# plc-6u-rs485-router.net
KiCad netlist of a schematic drawn in EAGLE
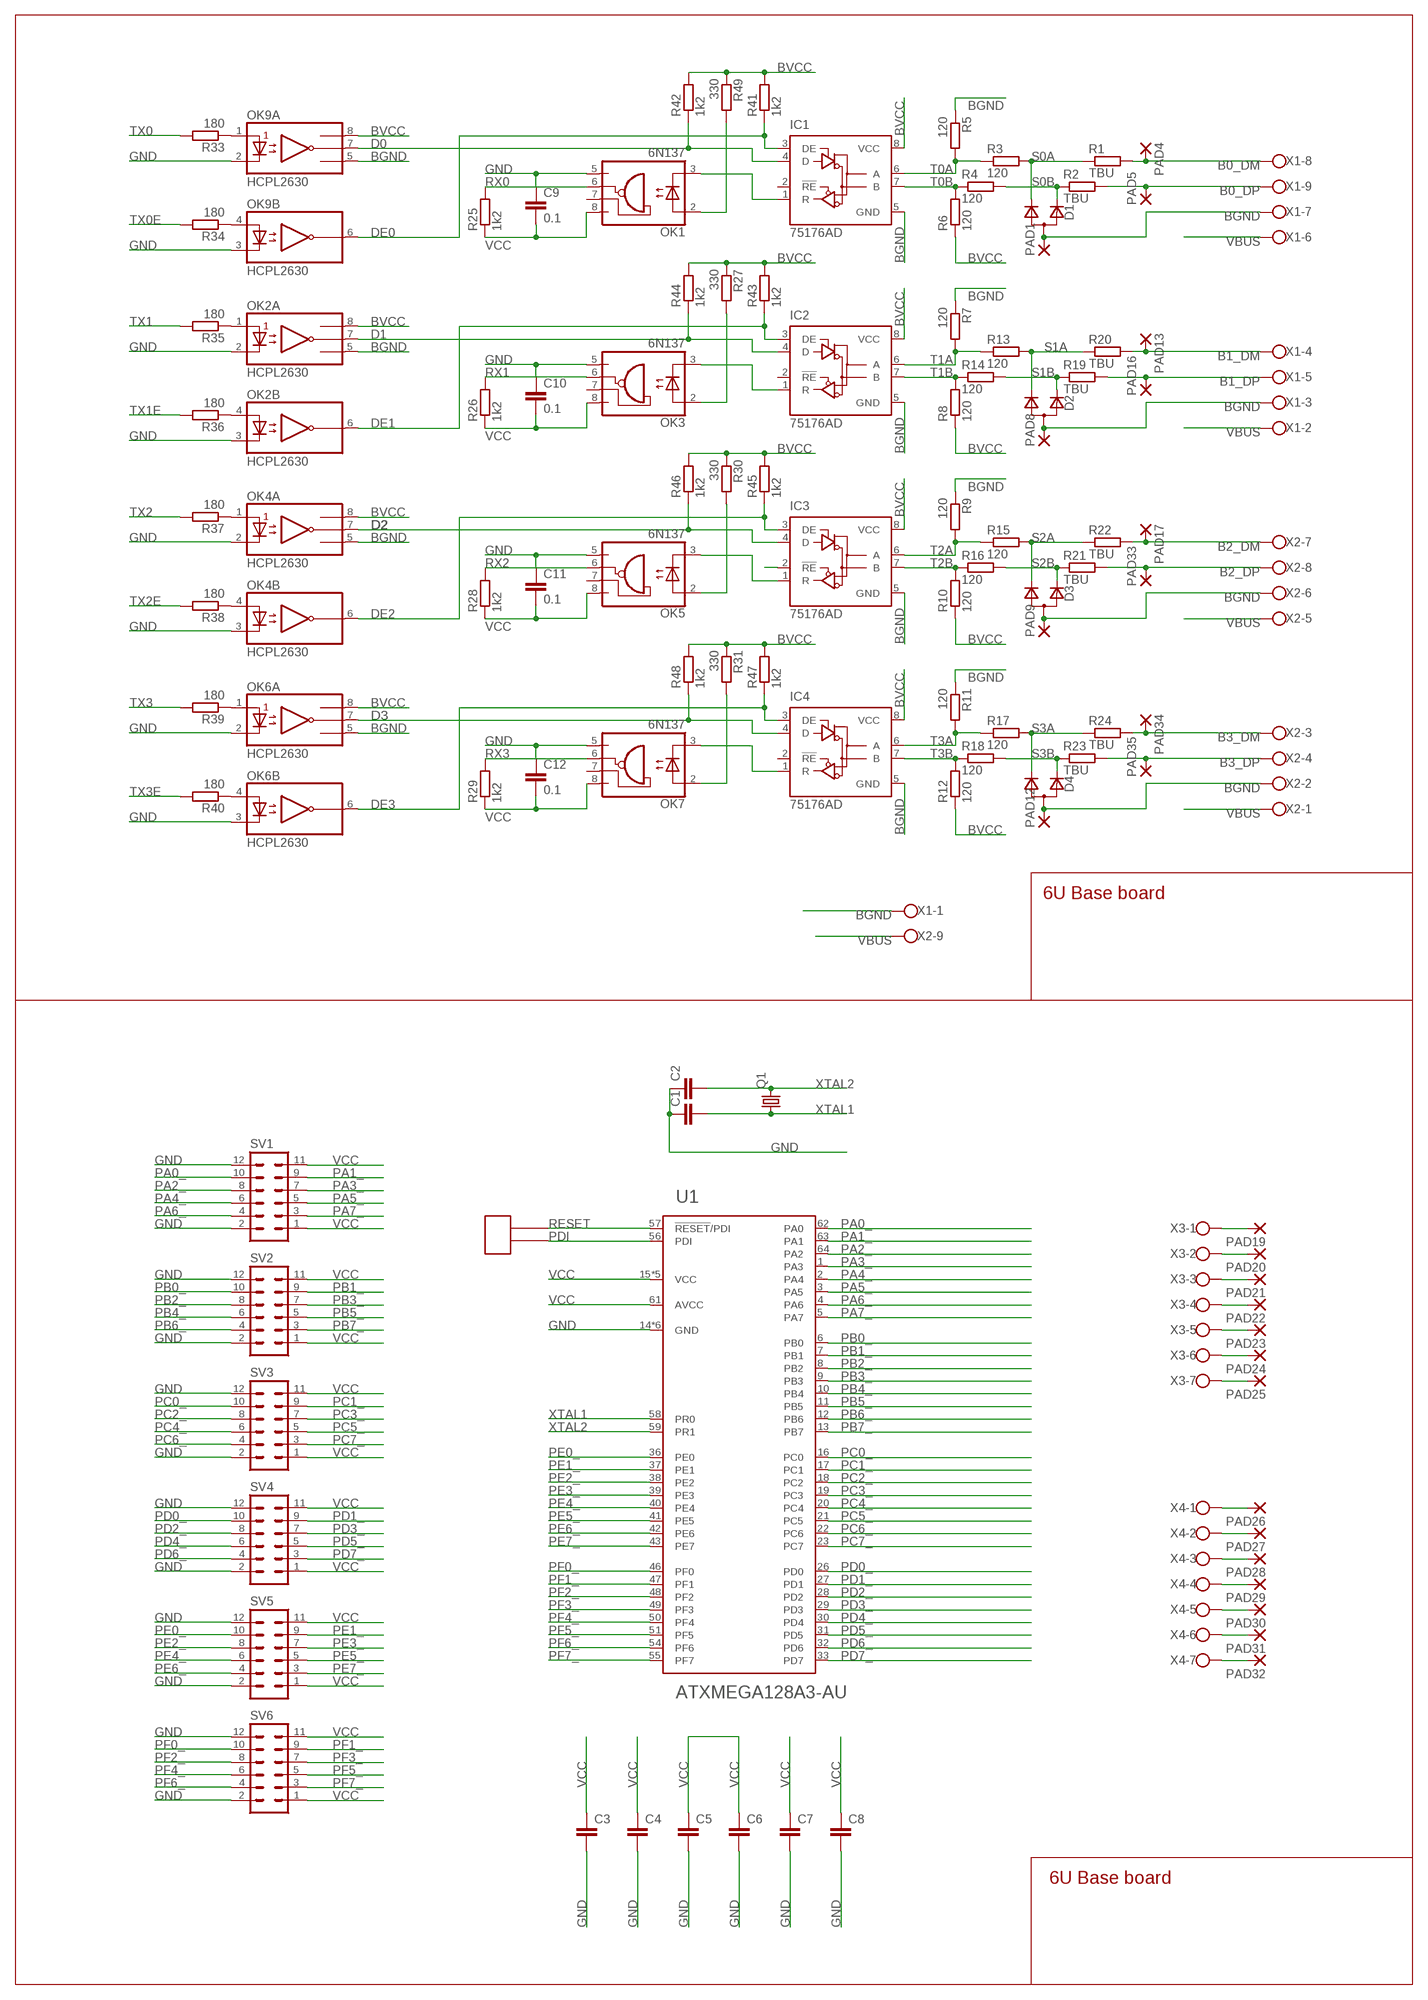
[diagram p0: schematic, sheet 1]

(export (version "E")
  (design (tool "Eeschema 10.0.6"))
  (components
    (comp (ref "C1")
      (value "C-EUC0805")
      (footprint "eagle-import:C0805")
      (libsource (lib "eagle-import") (part "C-EUC0805"))
    )
    (comp (ref "C2")
      (value "C-EUC0805")
      (footprint "eagle-import:C0805")
      (libsource (lib "eagle-import") (part "C-EUC0805"))
    )
    (comp (ref "C3")
      (value "C-EUC0603")
      (footprint "eagle-import:C0603")
      (libsource (lib "eagle-import") (part "C-EUC0603"))
    )
    (comp (ref "C4")
      (value "C-EUC0603")
      (footprint "eagle-import:C0603")
      (libsource (lib "eagle-import") (part "C-EUC0603"))
    )
    (comp (ref "C5")
      (value "C-EUC0603")
      (footprint "eagle-import:C0603")
      (libsource (lib "eagle-import") (part "C-EUC0603"))
    )
    (comp (ref "C6")
      (value "C-EUC0603")
      (footprint "eagle-import:C0603")
      (libsource (lib "eagle-import") (part "C-EUC0603"))
    )
    (comp (ref "C7")
      (value "C-EUC0603")
      (footprint "eagle-import:C0603")
      (libsource (lib "eagle-import") (part "C-EUC0603"))
    )
    (comp (ref "C8")
      (value "C-EUC0603")
      (footprint "eagle-import:C0603")
      (libsource (lib "eagle-import") (part "C-EUC0603"))
    )
    (comp (ref "C9")
      (value "0.1")
      (footprint "eagle-import:C0805")
      (libsource (lib "eagle-import") (part "C-EUC0805"))
    )
    (comp (ref "C10")
      (value "0.1")
      (footprint "eagle-import:C0805")
      (libsource (lib "eagle-import") (part "C-EUC0805"))
    )
    (comp (ref "C11")
      (value "0.1")
      (footprint "eagle-import:C0805")
      (libsource (lib "eagle-import") (part "C-EUC0805"))
    )
    (comp (ref "C12")
      (value "0.1")
      (footprint "eagle-import:C0805")
      (libsource (lib "eagle-import") (part "C-EUC0805"))
    )
    (comp (ref "D1")
      (value "D_2CSOT323")
      (footprint "eagle-import:SOT323")
      (libsource (lib "eagle-import") (part "D_2CSOT323"))
    )
    (comp (ref "D2")
      (value "D_2CSOT323")
      (footprint "eagle-import:SOT323")
      (fields (field (name "OC_FARNELL") "unknown") (field (name "OC_NEWARK") "unknown"))
      (libsource (lib "eagle-import") (part "D_2CSOT323"))
    )
    (comp (ref "D3")
      (value "D_2CSOT323")
      (footprint "eagle-import:SOT323")
      (fields (field (name "OC_FARNELL") "unknown") (field (name "OC_NEWARK") "unknown"))
      (libsource (lib "eagle-import") (part "D_2CSOT323"))
    )
    (comp (ref "D4")
      (value "D_2CSOT323")
      (footprint "eagle-import:SOT323")
      (fields (field (name "OC_FARNELL") "unknown") (field (name "OC_NEWARK") "unknown"))
      (libsource (lib "eagle-import") (part "D_2CSOT323"))
    )
    (comp (ref "IC1")
      (value "75176AD")
      (footprint "eagle-import:D_R-PDSO-G8")
      (libsource (lib "eagle-import") (part "75176AD"))
    )
    (comp (ref "IC2")
      (value "75176AD")
      (footprint "eagle-import:D_R-PDSO-G8")
      (libsource (lib "eagle-import") (part "75176AD"))
    )
    (comp (ref "IC3")
      (value "75176AD")
      (footprint "eagle-import:D_R-PDSO-G8")
      (libsource (lib "eagle-import") (part "75176AD"))
    )
    (comp (ref "IC4")
      (value "75176AD")
      (footprint "eagle-import:D_R-PDSO-G8")
      (libsource (lib "eagle-import") (part "75176AD"))
    )
    (comp (ref "OK1")
      (value "6N137")
      (footprint "eagle-import:DIL08")
      (libsource (lib "eagle-import") (part "6N137"))
    )
    (comp (ref "OK2")
      (value "HCPL2630")
      (footprint "eagle-import:DIL08")
      (fields (field (name "MF") "AGILENT TECHNOLOGIES") (field (name "MPN") "HCPL-2630-000E"))
      (libsource (lib "eagle-import") (part "HCPL2630"))
    )
    (comp (ref "OK3")
      (value "6N137")
      (footprint "eagle-import:DIL08")
      (libsource (lib "eagle-import") (part "6N137"))
    )
    (comp (ref "OK4")
      (value "HCPL2630")
      (footprint "eagle-import:DIL08")
      (fields (field (name "MF") "AGILENT TECHNOLOGIES") (field (name "MPN") "HCPL-2630-000E"))
      (libsource (lib "eagle-import") (part "HCPL2630"))
    )
    (comp (ref "OK5")
      (value "6N137")
      (footprint "eagle-import:DIL08")
      (libsource (lib "eagle-import") (part "6N137"))
    )
    (comp (ref "OK6")
      (value "HCPL2630")
      (footprint "eagle-import:DIL08")
      (fields (field (name "MF") "AGILENT TECHNOLOGIES") (field (name "MPN") "HCPL-2630-000E"))
      (libsource (lib "eagle-import") (part "HCPL2630"))
    )
    (comp (ref "OK7")
      (value "6N137")
      (footprint "eagle-import:DIL08")
      (libsource (lib "eagle-import") (part "6N137"))
    )
    (comp (ref "OK9")
      (value "HCPL2630")
      (footprint "eagle-import:DIL08")
      (fields (field (name "MF") "AGILENT TECHNOLOGIES") (field (name "MPN") "HCPL-2630-000E"))
      (libsource (lib "eagle-import") (part "HCPL2630"))
    )
    (comp (ref "PAD1")
      (value "2,54/0,8")
      (footprint "eagle-import:2,54_0,8")
      (libsource (lib "eagle-import") (part "2,54/0,8"))
    )
    (comp (ref "PAD4")
      (value "2,54/0,8")
      (footprint "eagle-import:2,54_0,8")
      (libsource (lib "eagle-import") (part "2,54/0,8"))
    )
    (comp (ref "PAD5")
      (value "2,54/0,8")
      (footprint "eagle-import:2,54_0,8")
      (libsource (lib "eagle-import") (part "2,54/0,8"))
    )
    (comp (ref "PAD8")
      (value "2,54/0,8")
      (footprint "eagle-import:2,54_0,8")
      (libsource (lib "eagle-import") (part "2,54/0,8"))
    )
    (comp (ref "PAD9")
      (value "2,54/0,8")
      (footprint "eagle-import:2,54_0,8")
      (libsource (lib "eagle-import") (part "2,54/0,8"))
    )
    (comp (ref "PAD12")
      (value "2,54/0,8")
      (footprint "eagle-import:2,54_0,8")
      (libsource (lib "eagle-import") (part "2,54/0,8"))
    )
    (comp (ref "PAD13")
      (value "2,54/0,8")
      (footprint "eagle-import:2,54_0,8")
      (libsource (lib "eagle-import") (part "2,54/0,8"))
    )
    (comp (ref "PAD16")
      (value "2,54/0,8")
      (footprint "eagle-import:2,54_0,8")
      (libsource (lib "eagle-import") (part "2,54/0,8"))
    )
    (comp (ref "PAD17")
      (value "2,54/0,8")
      (footprint "eagle-import:2,54_0,8")
      (libsource (lib "eagle-import") (part "2,54/0,8"))
    )
    (comp (ref "PAD19")
      (value "2,54/0,8")
      (footprint "eagle-import:2,54_0,8")
      (libsource (lib "eagle-import") (part "2,54/0,8"))
    )
    (comp (ref "PAD20")
      (value "2,54/0,8")
      (footprint "eagle-import:2,54_0,8")
      (libsource (lib "eagle-import") (part "2,54/0,8"))
    )
    (comp (ref "PAD21")
      (value "2,54/0,8")
      (footprint "eagle-import:2,54_0,8")
      (libsource (lib "eagle-import") (part "2,54/0,8"))
    )
    (comp (ref "PAD22")
      (value "2,54/0,8")
      (footprint "eagle-import:2,54_0,8")
      (libsource (lib "eagle-import") (part "2,54/0,8"))
    )
    (comp (ref "PAD23")
      (value "2,54/0,8")
      (footprint "eagle-import:2,54_0,8")
      (libsource (lib "eagle-import") (part "2,54/0,8"))
    )
    (comp (ref "PAD24")
      (value "2,54/0,8")
      (footprint "eagle-import:2,54_0,8")
      (libsource (lib "eagle-import") (part "2,54/0,8"))
    )
    (comp (ref "PAD25")
      (value "2,54/0,8")
      (footprint "eagle-import:2,54_0,8")
      (libsource (lib "eagle-import") (part "2,54/0,8"))
    )
    (comp (ref "PAD26")
      (value "2,54/0,8")
      (footprint "eagle-import:2,54_0,8")
      (libsource (lib "eagle-import") (part "2,54/0,8"))
    )
    (comp (ref "PAD27")
      (value "2,54/0,8")
      (footprint "eagle-import:2,54_0,8")
      (libsource (lib "eagle-import") (part "2,54/0,8"))
    )
    (comp (ref "PAD28")
      (value "2,54/0,8")
      (footprint "eagle-import:2,54_0,8")
      (libsource (lib "eagle-import") (part "2,54/0,8"))
    )
    (comp (ref "PAD29")
      (value "2,54/0,8")
      (footprint "eagle-import:2,54_0,8")
      (libsource (lib "eagle-import") (part "2,54/0,8"))
    )
    (comp (ref "PAD30")
      (value "2,54/0,8")
      (footprint "eagle-import:2,54_0,8")
      (libsource (lib "eagle-import") (part "2,54/0,8"))
    )
    (comp (ref "PAD31")
      (value "2,54/0,8")
      (footprint "eagle-import:2,54_0,8")
      (libsource (lib "eagle-import") (part "2,54/0,8"))
    )
    (comp (ref "PAD32")
      (value "2,54/0,8")
      (footprint "eagle-import:2,54_0,8")
      (libsource (lib "eagle-import") (part "2,54/0,8"))
    )
    (comp (ref "PAD33")
      (value "2,54/0,8")
      (footprint "eagle-import:2,54_0,8")
      (libsource (lib "eagle-import") (part "2,54/0,8"))
    )
    (comp (ref "PAD34")
      (value "2,54/0,8")
      (footprint "eagle-import:2,54_0,8")
      (libsource (lib "eagle-import") (part "2,54/0,8"))
    )
    (comp (ref "PAD35")
      (value "2,54/0,8")
      (footprint "eagle-import:2,54_0,8")
      (libsource (lib "eagle-import") (part "2,54/0,8"))
    )
    (comp (ref "Q1")
      (value "CRYSTALHC49S")
      (footprint "eagle-import:HC49_S")
      (libsource (lib "eagle-import") (part "CRYSTALHC49S"))
    )
    (comp (ref "R1")
      (value "TBU")
      (footprint "eagle-import:WSC2515")
      (libsource (lib "eagle-import") (part "R-EU_WSC2515"))
    )
    (comp (ref "R2")
      (value "TBU")
      (footprint "eagle-import:WSC2515")
      (libsource (lib "eagle-import") (part "R-EU_WSC2515"))
    )
    (comp (ref "R3")
      (value "120")
      (footprint "eagle-import:R0805")
      (libsource (lib "eagle-import") (part "R-EU_R0805"))
    )
    (comp (ref "R4")
      (value "120")
      (footprint "eagle-import:R0805")
      (libsource (lib "eagle-import") (part "R-EU_R0805"))
    )
    (comp (ref "R5")
      (value "120")
      (footprint "eagle-import:R0805")
      (libsource (lib "eagle-import") (part "R-EU_R0805"))
    )
    (comp (ref "R6")
      (value "120")
      (footprint "eagle-import:R0805")
      (libsource (lib "eagle-import") (part "R-EU_R0805"))
    )
    (comp (ref "R7")
      (value "120")
      (footprint "eagle-import:R0805")
      (libsource (lib "eagle-import") (part "R-EU_R0805"))
    )
    (comp (ref "R8")
      (value "120")
      (footprint "eagle-import:R0805")
      (libsource (lib "eagle-import") (part "R-EU_R0805"))
    )
    (comp (ref "R9")
      (value "120")
      (footprint "eagle-import:R0805")
      (libsource (lib "eagle-import") (part "R-EU_R0805"))
    )
    (comp (ref "R10")
      (value "120")
      (footprint "eagle-import:R0805")
      (libsource (lib "eagle-import") (part "R-EU_R0805"))
    )
    (comp (ref "R11")
      (value "120")
      (footprint "eagle-import:R0805")
      (libsource (lib "eagle-import") (part "R-EU_R0805"))
    )
    (comp (ref "R12")
      (value "120")
      (footprint "eagle-import:R0805")
      (libsource (lib "eagle-import") (part "R-EU_R0805"))
    )
    (comp (ref "R13")
      (value "120")
      (footprint "eagle-import:R0805")
      (libsource (lib "eagle-import") (part "R-EU_R0805"))
    )
    (comp (ref "R14")
      (value "120")
      (footprint "eagle-import:R0805")
      (libsource (lib "eagle-import") (part "R-EU_R0805"))
    )
    (comp (ref "R15")
      (value "120")
      (footprint "eagle-import:R0805")
      (libsource (lib "eagle-import") (part "R-EU_R0805"))
    )
    (comp (ref "R16")
      (value "120")
      (footprint "eagle-import:R0805")
      (libsource (lib "eagle-import") (part "R-EU_R0805"))
    )
    (comp (ref "R17")
      (value "120")
      (footprint "eagle-import:R0805")
      (libsource (lib "eagle-import") (part "R-EU_R0805"))
    )
    (comp (ref "R18")
      (value "120")
      (footprint "eagle-import:R0805")
      (libsource (lib "eagle-import") (part "R-EU_R0805"))
    )
    (comp (ref "R19")
      (value "TBU")
      (footprint "eagle-import:WSC2515")
      (libsource (lib "eagle-import") (part "R-EU_WSC2515"))
    )
    (comp (ref "R20")
      (value "TBU")
      (footprint "eagle-import:WSC2515")
      (libsource (lib "eagle-import") (part "R-EU_WSC2515"))
    )
    (comp (ref "R21")
      (value "TBU")
      (footprint "eagle-import:WSC2515")
      (libsource (lib "eagle-import") (part "R-EU_WSC2515"))
    )
    (comp (ref "R22")
      (value "TBU")
      (footprint "eagle-import:WSC2515")
      (libsource (lib "eagle-import") (part "R-EU_WSC2515"))
    )
    (comp (ref "R23")
      (value "TBU")
      (footprint "eagle-import:WSC2515")
      (libsource (lib "eagle-import") (part "R-EU_WSC2515"))
    )
    (comp (ref "R24")
      (value "TBU")
      (footprint "eagle-import:WSC2515")
      (libsource (lib "eagle-import") (part "R-EU_WSC2515"))
    )
    (comp (ref "R25")
      (value "1k2")
      (footprint "eagle-import:R0805")
      (libsource (lib "eagle-import") (part "R-EU_R0805"))
    )
    (comp (ref "R26")
      (value "1k2")
      (footprint "eagle-import:R0805")
      (libsource (lib "eagle-import") (part "R-EU_R0805"))
    )
    (comp (ref "R27")
      (value "330")
      (footprint "eagle-import:R0805")
      (libsource (lib "eagle-import") (part "R-EU_R0805"))
    )
    (comp (ref "R28")
      (value "1k2")
      (footprint "eagle-import:R0805")
      (libsource (lib "eagle-import") (part "R-EU_R0805"))
    )
    (comp (ref "R29")
      (value "1k2")
      (footprint "eagle-import:R0805")
      (libsource (lib "eagle-import") (part "R-EU_R0805"))
    )
    (comp (ref "R30")
      (value "330")
      (footprint "eagle-import:R0805")
      (libsource (lib "eagle-import") (part "R-EU_R0805"))
    )
    (comp (ref "R31")
      (value "330")
      (footprint "eagle-import:R0805")
      (libsource (lib "eagle-import") (part "R-EU_R0805"))
    )
    (comp (ref "R33")
      (value "180")
      (footprint "eagle-import:R0805")
      (libsource (lib "eagle-import") (part "R-EU_R0805"))
    )
    (comp (ref "R34")
      (value "180")
      (footprint "eagle-import:R0805")
      (libsource (lib "eagle-import") (part "R-EU_R0805"))
    )
    (comp (ref "R35")
      (value "180")
      (footprint "eagle-import:R0805")
      (libsource (lib "eagle-import") (part "R-EU_R0805"))
    )
    (comp (ref "R36")
      (value "180")
      (footprint "eagle-import:R0805")
      (libsource (lib "eagle-import") (part "R-EU_R0805"))
    )
    (comp (ref "R37")
      (value "180")
      (footprint "eagle-import:R0805")
      (libsource (lib "eagle-import") (part "R-EU_R0805"))
    )
    (comp (ref "R38")
      (value "180")
      (footprint "eagle-import:R0805")
      (libsource (lib "eagle-import") (part "R-EU_R0805"))
    )
    (comp (ref "R39")
      (value "180")
      (footprint "eagle-import:R0805")
      (libsource (lib "eagle-import") (part "R-EU_R0805"))
    )
    (comp (ref "R40")
      (value "180")
      (footprint "eagle-import:R0805")
      (libsource (lib "eagle-import") (part "R-EU_R0805"))
    )
    (comp (ref "R41")
      (value "1k2")
      (footprint "eagle-import:R0805")
      (libsource (lib "eagle-import") (part "R-EU_R0805"))
    )
    (comp (ref "R42")
      (value "1k2")
      (footprint "eagle-import:R0805")
      (libsource (lib "eagle-import") (part "R-EU_R0805"))
    )
    (comp (ref "R43")
      (value "1k2")
      (footprint "eagle-import:R0805")
      (libsource (lib "eagle-import") (part "R-EU_R0805"))
    )
    (comp (ref "R44")
      (value "1k2")
      (footprint "eagle-import:R0805")
      (libsource (lib "eagle-import") (part "R-EU_R0805"))
    )
    (comp (ref "R45")
      (value "1k2")
      (footprint "eagle-import:R0805")
      (libsource (lib "eagle-import") (part "R-EU_R0805"))
    )
    (comp (ref "R46")
      (value "1k2")
      (footprint "eagle-import:R0805")
      (libsource (lib "eagle-import") (part "R-EU_R0805"))
    )
    (comp (ref "R47")
      (value "1k2")
      (footprint "eagle-import:R0805")
      (libsource (lib "eagle-import") (part "R-EU_R0805"))
    )
    (comp (ref "R48")
      (value "1k2")
      (footprint "eagle-import:R0805")
      (libsource (lib "eagle-import") (part "R-EU_R0805"))
    )
    (comp (ref "R49")
      (value "330")
      (footprint "eagle-import:R0805")
      (libsource (lib "eagle-import") (part "R-EU_R0805"))
    )
    (comp (ref "SV1")
      (value "MA06-2")
      (footprint "eagle-import:MA06-2")
      (libsource (lib "eagle-import") (part "MA06-2"))
    )
    (comp (ref "SV2")
      (value "MA06-2")
      (footprint "eagle-import:MA06-2")
      (libsource (lib "eagle-import") (part "MA06-2"))
    )
    (comp (ref "SV3")
      (value "MA06-2")
      (footprint "eagle-import:MA06-2")
      (libsource (lib "eagle-import") (part "MA06-2"))
    )
    (comp (ref "SV4")
      (value "MA06-2")
      (footprint "eagle-import:MA06-2")
      (libsource (lib "eagle-import") (part "MA06-2"))
    )
    (comp (ref "SV5")
      (value "MA06-2")
      (footprint "eagle-import:MA06-2")
      (libsource (lib "eagle-import") (part "MA06-2"))
    )
    (comp (ref "SV6")
      (value "MA06-2")
      (footprint "eagle-import:MA06-2")
      (libsource (lib "eagle-import") (part "MA06-2"))
    )
    (comp (ref "U$1")
      (value "MA02-1")
      (footprint "eagle-import:MA02-1")
      (libsource (lib "eagle-import") (part "MA02-1"))
    )
    (comp (ref "U1")
      (value "ATXMEGA128A3-AU")
      (footprint "eagle-import:TQFP-64A-64")
      (libsource (lib "eagle-import") (part "ATXMEGA128A3-AU"))
    )
    (comp (ref "X1")
      (value "W237-09P")
      (footprint "eagle-import:W237-9P")
      (libsource (lib "eagle-import") (part "W237-09P"))
    )
    (comp (ref "X2")
      (value "W237-09P")
      (footprint "eagle-import:W237-9P")
      (libsource (lib "eagle-import") (part "W237-09P"))
    )
    (comp (ref "X3")
      (value "W237-07P")
      (footprint "eagle-import:W237-7P")
      (libsource (lib "eagle-import") (part "W237-07P"))
    )
    (comp (ref "X4")
      (value "W237-07P")
      (footprint "eagle-import:W237-7P")
      (libsource (lib "eagle-import") (part "W237-07P"))
    )
  )
  (nets
    (net (code "1") (name "/B0_DM") (class "Default")
      (node (ref "PAD4") (pin "1") (pinfunction "P_1") (pintype "passive"))
      (node (ref "R1") (pin "2") (pinfunction "2_2") (pintype "passive"))
      (node (ref "X1") (pin "8") (pinfunction "KL_8") (pintype "passive"))
    )
    (net (code "2") (name "/B0_DP") (class "Default")
      (node (ref "PAD5") (pin "1") (pinfunction "P_1") (pintype "passive"))
      (node (ref "R2") (pin "2") (pinfunction "2_2") (pintype "passive"))
      (node (ref "X1") (pin "9") (pinfunction "KL_9") (pintype "passive"))
    )
    (net (code "3") (name "/B1_DM") (class "Default")
      (node (ref "PAD16") (pin "1") (pinfunction "P_1") (pintype "passive"))
      (node (ref "R19") (pin "2") (pinfunction "2_2") (pintype "passive"))
      (node (ref "X1") (pin "5") (pinfunction "KL_5") (pintype "passive"))
    )
    (net (code "4") (name "/B1_DP") (class "Default")
      (node (ref "PAD13") (pin "1") (pinfunction "P_1") (pintype "passive"))
      (node (ref "R20") (pin "2") (pinfunction "2_2") (pintype "passive"))
      (node (ref "X1") (pin "4") (pinfunction "KL_4") (pintype "passive"))
    )
    (net (code "5") (name "/B2_DM") (class "Default")
      (node (ref "PAD17") (pin "1") (pinfunction "P_1") (pintype "passive"))
      (node (ref "R22") (pin "2") (pinfunction "2_2") (pintype "passive"))
      (node (ref "X2") (pin "7") (pinfunction "KL_7") (pintype "passive"))
    )
    (net (code "6") (name "/B2_DP") (class "Default")
      (node (ref "PAD33") (pin "1") (pinfunction "P_1") (pintype "passive"))
      (node (ref "R21") (pin "2") (pinfunction "2_2") (pintype "passive"))
      (node (ref "X2") (pin "8") (pinfunction "KL_8") (pintype "passive"))
    )
    (net (code "7") (name "/B3_DM") (class "Default")
      (node (ref "PAD34") (pin "1") (pinfunction "P_1") (pintype "passive"))
      (node (ref "R24") (pin "2") (pinfunction "2_2") (pintype "passive"))
      (node (ref "X2") (pin "3") (pinfunction "KL_3") (pintype "passive"))
    )
    (net (code "8") (name "/B3_DP") (class "Default")
      (node (ref "PAD35") (pin "1") (pinfunction "P_1") (pintype "passive"))
      (node (ref "R23") (pin "2") (pinfunction "2_2") (pintype "passive"))
      (node (ref "X2") (pin "4") (pinfunction "KL_4") (pintype "passive"))
    )
    (net (code "9") (name "/BGND") (class "Default")
      (node (ref "D1") (pin "1") (pinfunction "A_1") (pintype "passive"))
      (node (ref "D2") (pin "1") (pinfunction "A_1") (pintype "passive"))
      (node (ref "D3") (pin "1") (pinfunction "A_1") (pintype "passive"))
      (node (ref "D4") (pin "1") (pinfunction "A_1") (pintype "passive"))
      (node (ref "IC1") (pin "5") (pinfunction "GND_5") (pintype "power_in"))
      (node (ref "IC2") (pin "5") (pinfunction "GND_5") (pintype "power_in"))
      (node (ref "IC3") (pin "5") (pinfunction "GND_5") (pintype "power_in"))
      (node (ref "IC4") (pin "5") (pinfunction "GND_5") (pintype "power_in"))
      (node (ref "OK2") (pin "5") (pinfunction "GND_5") (pintype "passive"))
      (node (ref "OK4") (pin "5") (pinfunction "GND_5") (pintype "passive"))
      (node (ref "OK6") (pin "5") (pinfunction "GND_5") (pintype "passive"))
      (node (ref "OK9") (pin "5") (pinfunction "GND_5") (pintype "passive"))
      (node (ref "PAD1") (pin "1") (pinfunction "P_1") (pintype "passive"))
      (node (ref "PAD12") (pin "1") (pinfunction "P_1") (pintype "passive"))
      (node (ref "PAD8") (pin "1") (pinfunction "P_1") (pintype "passive"))
      (node (ref "PAD9") (pin "1") (pinfunction "P_1") (pintype "passive"))
      (node (ref "R11") (pin "1") (pinfunction "1_1") (pintype "passive"))
      (node (ref "R5") (pin "1") (pinfunction "1_1") (pintype "passive"))
      (node (ref "R7") (pin "1") (pinfunction "1_1") (pintype "passive"))
      (node (ref "R9") (pin "1") (pinfunction "1_1") (pintype "passive"))
      (node (ref "X1") (pin "1") (pinfunction "KL_1") (pintype "passive"))
      (node (ref "X1") (pin "3") (pinfunction "KL_3") (pintype "passive"))
      (node (ref "X1") (pin "7") (pinfunction "KL_7") (pintype "passive"))
      (node (ref "X2") (pin "2") (pinfunction "KL_2") (pintype "passive"))
      (node (ref "X2") (pin "6") (pinfunction "KL_6") (pintype "passive"))
    )
    (net (code "10") (name "/BVCC") (class "Default")
      (node (ref "IC1") (pin "8") (pinfunction "VCC_8") (pintype "power_in"))
      (node (ref "IC2") (pin "8") (pinfunction "VCC_8") (pintype "power_in"))
      (node (ref "IC3") (pin "8") (pinfunction "VCC_8") (pintype "power_in"))
      (node (ref "IC4") (pin "8") (pinfunction "VCC_8") (pintype "power_in"))
      (node (ref "OK2") (pin "8") (pinfunction "VCC_8") (pintype "passive"))
      (node (ref "OK4") (pin "8") (pinfunction "VCC_8") (pintype "passive"))
      (node (ref "OK6") (pin "8") (pinfunction "VCC_8") (pintype "passive"))
      (node (ref "OK9") (pin "8") (pinfunction "VCC_8") (pintype "passive"))
      (node (ref "R10") (pin "1") (pinfunction "1_1") (pintype "passive"))
      (node (ref "R12") (pin "1") (pinfunction "1_1") (pintype "passive"))
      (node (ref "R27") (pin "1") (pinfunction "1_1") (pintype "passive"))
      (node (ref "R30") (pin "1") (pinfunction "1_1") (pintype "passive"))
      (node (ref "R31") (pin "1") (pinfunction "1_1") (pintype "passive"))
      (node (ref "R41") (pin "2") (pinfunction "2_2") (pintype "passive"))
      (node (ref "R42") (pin "2") (pinfunction "2_2") (pintype "passive"))
      (node (ref "R43") (pin "2") (pinfunction "2_2") (pintype "passive"))
      (node (ref "R44") (pin "2") (pinfunction "2_2") (pintype "passive"))
      (node (ref "R45") (pin "2") (pinfunction "2_2") (pintype "passive"))
      (node (ref "R46") (pin "2") (pinfunction "2_2") (pintype "passive"))
      (node (ref "R47") (pin "2") (pinfunction "2_2") (pintype "passive"))
      (node (ref "R48") (pin "2") (pinfunction "2_2") (pintype "passive"))
      (node (ref "R49") (pin "1") (pinfunction "1_1") (pintype "passive"))
      (node (ref "R6") (pin "1") (pinfunction "1_1") (pintype "passive"))
      (node (ref "R8") (pin "1") (pinfunction "1_1") (pintype "passive"))
    )
    (net (code "11") (name "/D0") (class "Default")
      (node (ref "IC1") (pin "4") (pinfunction "D_4") (pintype "input"))
      (node (ref "OK9") (pin "7") (pinfunction "VO1_7") (pintype "passive"))
      (node (ref "R42") (pin "1") (pinfunction "1_1") (pintype "passive"))
    )
    (net (code "12") (name "/D1") (class "Default")
      (node (ref "IC2") (pin "4") (pinfunction "D_4") (pintype "input"))
      (node (ref "OK2") (pin "7") (pinfunction "VO1_7") (pintype "passive"))
      (node (ref "R44") (pin "1") (pinfunction "1_1") (pintype "passive"))
    )
    (net (code "13") (name "/D2") (class "Default")
      (node (ref "IC3") (pin "4") (pinfunction "D_4") (pintype "input"))
      (node (ref "OK4") (pin "7") (pinfunction "VO1_7") (pintype "passive"))
      (node (ref "R46") (pin "1") (pinfunction "1_1") (pintype "passive"))
    )
    (net (code "14") (name "/D3") (class "Default")
      (node (ref "IC4") (pin "4") (pinfunction "D_4") (pintype "input"))
      (node (ref "OK6") (pin "7") (pinfunction "VO1_7") (pintype "passive"))
      (node (ref "R48") (pin "1") (pinfunction "1_1") (pintype "passive"))
    )
    (net (code "15") (name "/DE0") (class "Default")
      (node (ref "IC1") (pin "3") (pinfunction "DE_3") (pintype "input"))
      (node (ref "OK9") (pin "6") (pinfunction "VO2_6") (pintype "passive"))
      (node (ref "R41") (pin "1") (pinfunction "1_1") (pintype "passive"))
    )
    (net (code "16") (name "/DE1") (class "Default")
      (node (ref "IC2") (pin "3") (pinfunction "DE_3") (pintype "input"))
      (node (ref "OK2") (pin "6") (pinfunction "VO2_6") (pintype "passive"))
      (node (ref "R43") (pin "1") (pinfunction "1_1") (pintype "passive"))
    )
    (net (code "17") (name "/DE2") (class "Default")
      (node (ref "IC3") (pin "3") (pinfunction "DE_3") (pintype "input"))
      (node (ref "OK4") (pin "6") (pinfunction "VO2_6") (pintype "passive"))
      (node (ref "R45") (pin "1") (pinfunction "1_1") (pintype "passive"))
    )
    (net (code "18") (name "/DE3") (class "Default")
      (node (ref "IC4") (pin "3") (pinfunction "DE_3") (pintype "input"))
      (node (ref "OK6") (pin "6") (pinfunction "VO2_6") (pintype "passive"))
      (node (ref "R47") (pin "1") (pinfunction "1_1") (pintype "passive"))
    )
    (net (code "19") (name "/GND") (class "Default")
      (node (ref "C1") (pin "1") (pinfunction "1_1") (pintype "passive"))
      (node (ref "C10") (pin "1") (pinfunction "1_1") (pintype "passive"))
      (node (ref "C11") (pin "1") (pinfunction "1_1") (pintype "passive"))
      (node (ref "C12") (pin "1") (pinfunction "1_1") (pintype "passive"))
      (node (ref "C2") (pin "1") (pinfunction "1_1") (pintype "passive"))
      (node (ref "C3") (pin "2") (pinfunction "2_2") (pintype "passive"))
      (node (ref "C4") (pin "2") (pinfunction "2_2") (pintype "passive"))
      (node (ref "C5") (pin "2") (pinfunction "2_2") (pintype "passive"))
      (node (ref "C6") (pin "2") (pinfunction "2_2") (pintype "passive"))
      (node (ref "C7") (pin "2") (pinfunction "2_2") (pintype "passive"))
      (node (ref "C8") (pin "2") (pinfunction "2_2") (pintype "passive"))
      (node (ref "C9") (pin "1") (pinfunction "1_1") (pintype "passive"))
      (node (ref "OK1") (pin "5") (pinfunction "GND_5") (pintype "passive"))
      (node (ref "OK2") (pin "2") (pinfunction "C1_2") (pintype "passive"))
      (node (ref "OK2") (pin "3") (pinfunction "C2_3") (pintype "passive"))
      (node (ref "OK3") (pin "5") (pinfunction "GND_5") (pintype "passive"))
      (node (ref "OK4") (pin "2") (pinfunction "C1_2") (pintype "passive"))
      (node (ref "OK4") (pin "3") (pinfunction "C2_3") (pintype "passive"))
      (node (ref "OK5") (pin "5") (pinfunction "GND_5") (pintype "passive"))
      (node (ref "OK6") (pin "2") (pinfunction "C1_2") (pintype "passive"))
      (node (ref "OK6") (pin "3") (pinfunction "C2_3") (pintype "passive"))
      (node (ref "OK7") (pin "5") (pinfunction "GND_5") (pintype "passive"))
      (node (ref "OK9") (pin "2") (pinfunction "C1_2") (pintype "passive"))
      (node (ref "OK9") (pin "3") (pinfunction "C2_3") (pintype "passive"))
      (node (ref "SV1") (pin "12") (pinfunction "12_12") (pintype "passive"))
      (node (ref "SV1") (pin "2") (pinfunction "2_2") (pintype "passive"))
      (node (ref "SV2") (pin "12") (pinfunction "12_12") (pintype "passive"))
      (node (ref "SV2") (pin "2") (pinfunction "2_2") (pintype "passive"))
      (node (ref "SV3") (pin "12") (pinfunction "12_12") (pintype "passive"))
      (node (ref "SV3") (pin "2") (pinfunction "2_2") (pintype "passive"))
      (node (ref "SV4") (pin "12") (pinfunction "12_12") (pintype "passive"))
      (node (ref "SV4") (pin "2") (pinfunction "2_2") (pintype "passive"))
      (node (ref "SV5") (pin "12") (pinfunction "12_12") (pintype "passive"))
      (node (ref "SV5") (pin "2") (pinfunction "2_2") (pintype "passive"))
      (node (ref "SV6") (pin "12") (pinfunction "12_12") (pintype "passive"))
      (node (ref "SV6") (pin "2") (pinfunction "2_2") (pintype "passive"))
      (node (ref "U1") (pin "14") (pinfunction "GND_14") (pintype "power_in"))
      (node (ref "U1") (pin "24") (pinfunction "GND_24") (pintype "power_in"))
      (node (ref "U1") (pin "34") (pinfunction "GND_34") (pintype "power_in"))
      (node (ref "U1") (pin "44") (pinfunction "GND_44") (pintype "power_in"))
      (node (ref "U1") (pin "52") (pinfunction "GND_52") (pintype "power_in"))
      (node (ref "U1") (pin "60") (pinfunction "GND_60") (pintype "power_in"))
    )
    (net (code "20") (name "/PA0_") (class "Default")
      (node (ref "SV1") (pin "10") (pinfunction "10_10") (pintype "passive"))
      (node (ref "U1") (pin "62") (pinfunction "PA0_62") (pintype "bidirectional"))
    )
    (net (code "21") (name "/PA1_") (class "Default")
      (node (ref "SV1") (pin "9") (pinfunction "9_9") (pintype "passive"))
      (node (ref "U1") (pin "63") (pinfunction "PA1_63") (pintype "bidirectional"))
    )
    (net (code "22") (name "/PA2_") (class "Default")
      (node (ref "SV1") (pin "8") (pinfunction "8_8") (pintype "passive"))
      (node (ref "U1") (pin "64") (pinfunction "PA2_64") (pintype "bidirectional"))
    )
    (net (code "23") (name "/PA3_") (class "Default")
      (node (ref "SV1") (pin "7") (pinfunction "7_7") (pintype "passive"))
      (node (ref "U1") (pin "1") (pinfunction "PA3_1") (pintype "bidirectional"))
    )
    (net (code "24") (name "/PA4_") (class "Default")
      (node (ref "SV1") (pin "6") (pinfunction "6_6") (pintype "passive"))
      (node (ref "U1") (pin "2") (pinfunction "PA4_2") (pintype "bidirectional"))
    )
    (net (code "25") (name "/PA5_") (class "Default")
      (node (ref "SV1") (pin "5") (pinfunction "5_5") (pintype "passive"))
      (node (ref "U1") (pin "3") (pinfunction "PA5_3") (pintype "bidirectional"))
    )
    (net (code "26") (name "/PA6_") (class "Default")
      (node (ref "SV1") (pin "4") (pinfunction "4_4") (pintype "passive"))
      (node (ref "U1") (pin "4") (pinfunction "PA6_4") (pintype "bidirectional"))
    )
    (net (code "27") (name "/PA7_") (class "Default")
      (node (ref "SV1") (pin "3") (pinfunction "3_3") (pintype "passive"))
      (node (ref "U1") (pin "5") (pinfunction "PA7_5") (pintype "bidirectional"))
    )
    (net (code "28") (name "/PB0_") (class "Default")
      (node (ref "SV2") (pin "10") (pinfunction "10_10") (pintype "passive"))
      (node (ref "U1") (pin "6") (pinfunction "PB0_6") (pintype "bidirectional"))
    )
    (net (code "29") (name "/PB1_") (class "Default")
      (node (ref "SV2") (pin "9") (pinfunction "9_9") (pintype "passive"))
      (node (ref "U1") (pin "7") (pinfunction "PB1_7") (pintype "bidirectional"))
    )
    (net (code "30") (name "/PB2_") (class "Default")
      (node (ref "SV2") (pin "8") (pinfunction "8_8") (pintype "passive"))
      (node (ref "U1") (pin "8") (pinfunction "PB2_8") (pintype "bidirectional"))
    )
    (net (code "31") (name "/PB3_") (class "Default")
      (node (ref "SV2") (pin "7") (pinfunction "7_7") (pintype "passive"))
      (node (ref "U1") (pin "9") (pinfunction "PB3_9") (pintype "bidirectional"))
    )
    (net (code "32") (name "/PB4_") (class "Default")
      (node (ref "SV2") (pin "6") (pinfunction "6_6") (pintype "passive"))
      (node (ref "U1") (pin "10") (pinfunction "PB4_10") (pintype "bidirectional"))
    )
    (net (code "33") (name "/PB5_") (class "Default")
      (node (ref "SV2") (pin "5") (pinfunction "5_5") (pintype "passive"))
      (node (ref "U1") (pin "11") (pinfunction "PB5_11") (pintype "bidirectional"))
    )
    (net (code "34") (name "/PB6_") (class "Default")
      (node (ref "SV2") (pin "4") (pinfunction "4_4") (pintype "passive"))
      (node (ref "U1") (pin "12") (pinfunction "PB6_12") (pintype "bidirectional"))
    )
    (net (code "35") (name "/PB7_") (class "Default")
      (node (ref "SV2") (pin "3") (pinfunction "3_3") (pintype "passive"))
      (node (ref "U1") (pin "13") (pinfunction "PB7_13") (pintype "bidirectional"))
    )
    (net (code "36") (name "/PC0_") (class "Default")
      (node (ref "SV3") (pin "10") (pinfunction "10_10") (pintype "passive"))
      (node (ref "U1") (pin "16") (pinfunction "PC0_16") (pintype "bidirectional"))
    )
    (net (code "37") (name "/PC1_") (class "Default")
      (node (ref "SV3") (pin "9") (pinfunction "9_9") (pintype "passive"))
      (node (ref "U1") (pin "17") (pinfunction "PC1_17") (pintype "bidirectional"))
    )
    (net (code "38") (name "/PC2_") (class "Default")
      (node (ref "SV3") (pin "8") (pinfunction "8_8") (pintype "passive"))
      (node (ref "U1") (pin "18") (pinfunction "PC2_18") (pintype "bidirectional"))
    )
    (net (code "39") (name "/PC3_") (class "Default")
      (node (ref "SV3") (pin "7") (pinfunction "7_7") (pintype "passive"))
      (node (ref "U1") (pin "19") (pinfunction "PC3_19") (pintype "bidirectional"))
    )
    (net (code "40") (name "/PC4_") (class "Default")
      (node (ref "SV3") (pin "6") (pinfunction "6_6") (pintype "passive"))
      (node (ref "U1") (pin "20") (pinfunction "PC4_20") (pintype "bidirectional"))
    )
    (net (code "41") (name "/PC5_") (class "Default")
      (node (ref "SV3") (pin "5") (pinfunction "5_5") (pintype "passive"))
      (node (ref "U1") (pin "21") (pinfunction "PC5_21") (pintype "bidirectional"))
    )
    (net (code "42") (name "/PC6_") (class "Default")
      (node (ref "SV3") (pin "4") (pinfunction "4_4") (pintype "passive"))
      (node (ref "U1") (pin "22") (pinfunction "PC6_22") (pintype "bidirectional"))
    )
    (net (code "43") (name "/PC7_") (class "Default")
      (node (ref "SV3") (pin "3") (pinfunction "3_3") (pintype "passive"))
      (node (ref "U1") (pin "23") (pinfunction "PC7_23") (pintype "bidirectional"))
    )
    (net (code "44") (name "/PD0_") (class "Default")
      (node (ref "SV4") (pin "10") (pinfunction "10_10") (pintype "passive"))
      (node (ref "U1") (pin "26") (pinfunction "PD0_26") (pintype "bidirectional"))
    )
    (net (code "45") (name "/PD1_") (class "Default")
      (node (ref "SV4") (pin "9") (pinfunction "9_9") (pintype "passive"))
      (node (ref "U1") (pin "27") (pinfunction "PD1_27") (pintype "bidirectional"))
    )
    (net (code "46") (name "/PD2_") (class "Default")
      (node (ref "SV4") (pin "8") (pinfunction "8_8") (pintype "passive"))
      (node (ref "U1") (pin "28") (pinfunction "PD2_28") (pintype "bidirectional"))
    )
    (net (code "47") (name "/PD3_") (class "Default")
      (node (ref "SV4") (pin "7") (pinfunction "7_7") (pintype "passive"))
      (node (ref "U1") (pin "29") (pinfunction "PD3_29") (pintype "bidirectional"))
    )
    (net (code "48") (name "/PD4_") (class "Default")
      (node (ref "SV4") (pin "6") (pinfunction "6_6") (pintype "passive"))
      (node (ref "U1") (pin "30") (pinfunction "PD4_30") (pintype "bidirectional"))
    )
    (net (code "49") (name "/PD5_") (class "Default")
      (node (ref "SV4") (pin "5") (pinfunction "5_5") (pintype "passive"))
      (node (ref "U1") (pin "31") (pinfunction "PD5_31") (pintype "bidirectional"))
    )
    (net (code "50") (name "/PD6_") (class "Default")
      (node (ref "SV4") (pin "4") (pinfunction "4_4") (pintype "passive"))
      (node (ref "U1") (pin "32") (pinfunction "PD6_32") (pintype "bidirectional"))
    )
    (net (code "51") (name "/PD7_") (class "Default")
      (node (ref "SV4") (pin "3") (pinfunction "3_3") (pintype "passive"))
      (node (ref "U1") (pin "33") (pinfunction "PD7_33") (pintype "bidirectional"))
    )
    (net (code "52") (name "/PDI") (class "Default")
      (node (ref "U$1") (pin "P1") (pinfunction "P1_P1") (pintype "bidirectional"))
      (node (ref "U1") (pin "56") (pinfunction "PDI_56") (pintype "bidirectional"))
    )
    (net (code "53") (name "/PE0_") (class "Default")
      (node (ref "SV5") (pin "10") (pinfunction "10_10") (pintype "passive"))
      (node (ref "U1") (pin "36") (pinfunction "PE0_36") (pintype "bidirectional"))
    )
    (net (code "54") (name "/PE1_") (class "Default")
      (node (ref "SV5") (pin "9") (pinfunction "9_9") (pintype "passive"))
      (node (ref "U1") (pin "37") (pinfunction "PE1_37") (pintype "bidirectional"))
    )
    (net (code "55") (name "/PE2_") (class "Default")
      (node (ref "SV5") (pin "8") (pinfunction "8_8") (pintype "passive"))
      (node (ref "U1") (pin "38") (pinfunction "PE2_38") (pintype "bidirectional"))
    )
    (net (code "56") (name "/PE3_") (class "Default")
      (node (ref "SV5") (pin "7") (pinfunction "7_7") (pintype "passive"))
      (node (ref "U1") (pin "39") (pinfunction "PE3_39") (pintype "bidirectional"))
    )
    (net (code "57") (name "/PE4_") (class "Default")
      (node (ref "SV5") (pin "6") (pinfunction "6_6") (pintype "passive"))
      (node (ref "U1") (pin "40") (pinfunction "PE4_40") (pintype "bidirectional"))
    )
    (net (code "58") (name "/PE5_") (class "Default")
      (node (ref "SV5") (pin "5") (pinfunction "5_5") (pintype "passive"))
      (node (ref "U1") (pin "41") (pinfunction "PE5_41") (pintype "bidirectional"))
    )
    (net (code "59") (name "/PE6_") (class "Default")
      (node (ref "SV5") (pin "4") (pinfunction "4_4") (pintype "passive"))
      (node (ref "U1") (pin "42") (pinfunction "PE6_42") (pintype "bidirectional"))
    )
    (net (code "60") (name "/PE7_") (class "Default")
      (node (ref "SV5") (pin "3") (pinfunction "3_3") (pintype "passive"))
      (node (ref "U1") (pin "43") (pinfunction "PE7_43") (pintype "bidirectional"))
    )
    (net (code "61") (name "/PF0_") (class "Default")
      (node (ref "SV6") (pin "10") (pinfunction "10_10") (pintype "passive"))
      (node (ref "U1") (pin "46") (pinfunction "PF0_46") (pintype "bidirectional"))
    )
    (net (code "62") (name "/PF1_") (class "Default")
      (node (ref "SV6") (pin "9") (pinfunction "9_9") (pintype "passive"))
      (node (ref "U1") (pin "47") (pinfunction "PF1_47") (pintype "bidirectional"))
    )
    (net (code "63") (name "/PF2_") (class "Default")
      (node (ref "SV6") (pin "8") (pinfunction "8_8") (pintype "passive"))
      (node (ref "U1") (pin "48") (pinfunction "PF2_48") (pintype "bidirectional"))
    )
    (net (code "64") (name "/PF3_") (class "Default")
      (node (ref "SV6") (pin "7") (pinfunction "7_7") (pintype "passive"))
      (node (ref "U1") (pin "49") (pinfunction "PF3_49") (pintype "bidirectional"))
    )
    (net (code "65") (name "/PF4_") (class "Default")
      (node (ref "SV6") (pin "6") (pinfunction "6_6") (pintype "passive"))
      (node (ref "U1") (pin "50") (pinfunction "PF4_50") (pintype "bidirectional"))
    )
    (net (code "66") (name "/PF5_") (class "Default")
      (node (ref "SV6") (pin "5") (pinfunction "5_5") (pintype "passive"))
      (node (ref "U1") (pin "51") (pinfunction "PF5_51") (pintype "bidirectional"))
    )
    (net (code "67") (name "/PF6_") (class "Default")
      (node (ref "SV6") (pin "4") (pinfunction "4_4") (pintype "passive"))
      (node (ref "U1") (pin "54") (pinfunction "PF6_54") (pintype "bidirectional"))
    )
    (net (code "68") (name "/PF7_") (class "Default")
      (node (ref "SV6") (pin "3") (pinfunction "3_3") (pintype "passive"))
      (node (ref "U1") (pin "55") (pinfunction "PF7_55") (pintype "bidirectional"))
    )
    (net (code "69") (name "/RESET") (class "Default")
      (node (ref "U$1") (pin "P2") (pinfunction "P2_P2") (pintype "bidirectional"))
      (node (ref "U1") (pin "57") (pinfunction "~{RESET}/PDI_57") (pintype "bidirectional"))
    )
    (net (code "70") (name "/RX0") (class "Default")
      (node (ref "OK1") (pin "6") (pinfunction "VO_6") (pintype "passive"))
      (node (ref "R25") (pin "2") (pinfunction "2_2") (pintype "passive"))
    )
    (net (code "71") (name "/RX1") (class "Default")
      (node (ref "OK3") (pin "6") (pinfunction "VO_6") (pintype "passive"))
      (node (ref "R26") (pin "2") (pinfunction "2_2") (pintype "passive"))
    )
    (net (code "72") (name "/RX2") (class "Default")
      (node (ref "OK5") (pin "6") (pinfunction "VO_6") (pintype "passive"))
      (node (ref "R28") (pin "2") (pinfunction "2_2") (pintype "passive"))
    )
    (net (code "73") (name "/RX3") (class "Default")
      (node (ref "OK7") (pin "6") (pinfunction "VO_6") (pintype "passive"))
      (node (ref "R29") (pin "2") (pinfunction "2_2") (pintype "passive"))
    )
    (net (code "74") (name "/S0A") (class "Default")
      (node (ref "D1") (pin "3") (pinfunction "C2_3") (pintype "passive"))
      (node (ref "R1") (pin "1") (pinfunction "1_1") (pintype "passive"))
      (node (ref "R3") (pin "2") (pinfunction "2_2") (pintype "passive"))
    )
    (net (code "75") (name "/S0B") (class "Default")
      (node (ref "D1") (pin "2") (pinfunction "C1_2") (pintype "passive"))
      (node (ref "R2") (pin "1") (pinfunction "1_1") (pintype "passive"))
      (node (ref "R4") (pin "2") (pinfunction "2_2") (pintype "passive"))
    )
    (net (code "76") (name "/S1A") (class "Default")
      (node (ref "D2") (pin "3") (pinfunction "C2_3") (pintype "passive"))
      (node (ref "R13") (pin "2") (pinfunction "2_2") (pintype "passive"))
      (node (ref "R20") (pin "1") (pinfunction "1_1") (pintype "passive"))
    )
    (net (code "77") (name "/S1B") (class "Default")
      (node (ref "D2") (pin "2") (pinfunction "C1_2") (pintype "passive"))
      (node (ref "R14") (pin "2") (pinfunction "2_2") (pintype "passive"))
      (node (ref "R19") (pin "1") (pinfunction "1_1") (pintype "passive"))
    )
    (net (code "78") (name "/S2A") (class "Default")
      (node (ref "D3") (pin "3") (pinfunction "C2_3") (pintype "passive"))
      (node (ref "R15") (pin "2") (pinfunction "2_2") (pintype "passive"))
      (node (ref "R22") (pin "1") (pinfunction "1_1") (pintype "passive"))
    )
    (net (code "79") (name "/S2B") (class "Default")
      (node (ref "D3") (pin "2") (pinfunction "C1_2") (pintype "passive"))
      (node (ref "R16") (pin "2") (pinfunction "2_2") (pintype "passive"))
      (node (ref "R21") (pin "1") (pinfunction "1_1") (pintype "passive"))
    )
    (net (code "80") (name "/S3A") (class "Default")
      (node (ref "D4") (pin "3") (pinfunction "C2_3") (pintype "passive"))
      (node (ref "R17") (pin "2") (pinfunction "2_2") (pintype "passive"))
      (node (ref "R24") (pin "1") (pinfunction "1_1") (pintype "passive"))
    )
    (net (code "81") (name "/S3B") (class "Default")
      (node (ref "D4") (pin "2") (pinfunction "C1_2") (pintype "passive"))
      (node (ref "R18") (pin "2") (pinfunction "2_2") (pintype "passive"))
      (node (ref "R23") (pin "1") (pinfunction "1_1") (pintype "passive"))
    )
    (net (code "82") (name "/T0A") (class "Default")
      (node (ref "IC1") (pin "6") (pinfunction "A_6") (pintype "output"))
      (node (ref "R3") (pin "1") (pinfunction "1_1") (pintype "passive"))
      (node (ref "R5") (pin "2") (pinfunction "2_2") (pintype "passive"))
    )
    (net (code "83") (name "/T0B") (class "Default")
      (node (ref "IC1") (pin "7") (pinfunction "B_7") (pintype "output"))
      (node (ref "R4") (pin "1") (pinfunction "1_1") (pintype "passive"))
      (node (ref "R6") (pin "2") (pinfunction "2_2") (pintype "passive"))
    )
    (net (code "84") (name "/T1A") (class "Default")
      (node (ref "IC2") (pin "6") (pinfunction "A_6") (pintype "output"))
      (node (ref "R13") (pin "1") (pinfunction "1_1") (pintype "passive"))
      (node (ref "R7") (pin "2") (pinfunction "2_2") (pintype "passive"))
    )
    (net (code "85") (name "/T1B") (class "Default")
      (node (ref "IC2") (pin "7") (pinfunction "B_7") (pintype "output"))
      (node (ref "R14") (pin "1") (pinfunction "1_1") (pintype "passive"))
      (node (ref "R8") (pin "2") (pinfunction "2_2") (pintype "passive"))
    )
    (net (code "86") (name "/T2A") (class "Default")
      (node (ref "IC3") (pin "6") (pinfunction "A_6") (pintype "output"))
      (node (ref "R15") (pin "1") (pinfunction "1_1") (pintype "passive"))
      (node (ref "R9") (pin "2") (pinfunction "2_2") (pintype "passive"))
    )
    (net (code "87") (name "/T2B") (class "Default")
      (node (ref "IC3") (pin "7") (pinfunction "B_7") (pintype "output"))
      (node (ref "R10") (pin "2") (pinfunction "2_2") (pintype "passive"))
      (node (ref "R16") (pin "1") (pinfunction "1_1") (pintype "passive"))
    )
    (net (code "88") (name "/T3A") (class "Default")
      (node (ref "IC4") (pin "6") (pinfunction "A_6") (pintype "output"))
      (node (ref "R11") (pin "2") (pinfunction "2_2") (pintype "passive"))
      (node (ref "R17") (pin "1") (pinfunction "1_1") (pintype "passive"))
    )
    (net (code "89") (name "/T3B") (class "Default")
      (node (ref "IC4") (pin "7") (pinfunction "B_7") (pintype "output"))
      (node (ref "R12") (pin "2") (pinfunction "2_2") (pintype "passive"))
      (node (ref "R18") (pin "1") (pinfunction "1_1") (pintype "passive"))
    )
    (net (code "90") (name "/TX0") (class "Default")
      (node (ref "R33") (pin "2") (pinfunction "2_2") (pintype "passive"))
    )
    (net (code "91") (name "/TX0E") (class "Default")
      (node (ref "R34") (pin "2") (pinfunction "2_2") (pintype "passive"))
    )
    (net (code "92") (name "/TX1") (class "Default")
      (node (ref "R35") (pin "2") (pinfunction "2_2") (pintype "passive"))
    )
    (net (code "93") (name "/TX1E") (class "Default")
      (node (ref "R36") (pin "2") (pinfunction "2_2") (pintype "passive"))
    )
    (net (code "94") (name "/TX2") (class "Default")
      (node (ref "R37") (pin "2") (pinfunction "2_2") (pintype "passive"))
    )
    (net (code "95") (name "/TX2E") (class "Default")
      (node (ref "R38") (pin "2") (pinfunction "2_2") (pintype "passive"))
    )
    (net (code "96") (name "/TX3") (class "Default")
      (node (ref "R39") (pin "2") (pinfunction "2_2") (pintype "passive"))
    )
    (net (code "97") (name "/TX3E") (class "Default")
      (node (ref "R40") (pin "2") (pinfunction "2_2") (pintype "passive"))
    )
    (net (code "98") (name "/VBUS") (class "Default")
      (node (ref "X1") (pin "2") (pinfunction "KL_2") (pintype "passive"))
      (node (ref "X1") (pin "6") (pinfunction "KL_6") (pintype "passive"))
      (node (ref "X2") (pin "1") (pinfunction "KL_1") (pintype "passive"))
      (node (ref "X2") (pin "5") (pinfunction "KL_5") (pintype "passive"))
      (node (ref "X2") (pin "9") (pinfunction "KL_9") (pintype "passive"))
    )
    (net (code "99") (name "/VCC") (class "Default")
      (node (ref "C10") (pin "2") (pinfunction "2_2") (pintype "passive"))
      (node (ref "C11") (pin "2") (pinfunction "2_2") (pintype "passive"))
      (node (ref "C12") (pin "2") (pinfunction "2_2") (pintype "passive"))
      (node (ref "C3") (pin "1") (pinfunction "1_1") (pintype "passive"))
      (node (ref "C4") (pin "1") (pinfunction "1_1") (pintype "passive"))
      (node (ref "C5") (pin "1") (pinfunction "1_1") (pintype "passive"))
      (node (ref "C6") (pin "1") (pinfunction "1_1") (pintype "passive"))
      (node (ref "C7") (pin "1") (pinfunction "1_1") (pintype "passive"))
      (node (ref "C8") (pin "1") (pinfunction "1_1") (pintype "passive"))
      (node (ref "C9") (pin "2") (pinfunction "2_2") (pintype "passive"))
      (node (ref "OK1") (pin "8") (pinfunction "VCC_8") (pintype "passive"))
      (node (ref "OK3") (pin "8") (pinfunction "VCC_8") (pintype "passive"))
      (node (ref "OK5") (pin "8") (pinfunction "VCC_8") (pintype "passive"))
      (node (ref "OK7") (pin "8") (pinfunction "VCC_8") (pintype "passive"))
      (node (ref "R25") (pin "1") (pinfunction "1_1") (pintype "passive"))
      (node (ref "R26") (pin "1") (pinfunction "1_1") (pintype "passive"))
      (node (ref "R28") (pin "1") (pinfunction "1_1") (pintype "passive"))
      (node (ref "R29") (pin "1") (pinfunction "1_1") (pintype "passive"))
      (node (ref "SV1") (pin "1") (pinfunction "1_1") (pintype "passive"))
      (node (ref "SV1") (pin "11") (pinfunction "11_11") (pintype "passive"))
      (node (ref "SV2") (pin "1") (pinfunction "1_1") (pintype "passive"))
      (node (ref "SV2") (pin "11") (pinfunction "11_11") (pintype "passive"))
      (node (ref "SV3") (pin "1") (pinfunction "1_1") (pintype "passive"))
      (node (ref "SV3") (pin "11") (pinfunction "11_11") (pintype "passive"))
      (node (ref "SV4") (pin "1") (pinfunction "1_1") (pintype "passive"))
      (node (ref "SV4") (pin "11") (pinfunction "11_11") (pintype "passive"))
      (node (ref "SV5") (pin "1") (pinfunction "1_1") (pintype "passive"))
      (node (ref "SV5") (pin "11") (pinfunction "11_11") (pintype "passive"))
      (node (ref "SV6") (pin "1") (pinfunction "1_1") (pintype "passive"))
      (node (ref "SV6") (pin "11") (pinfunction "11_11") (pintype "passive"))
      (node (ref "U1") (pin "15") (pinfunction "VCC_15") (pintype "power_in"))
      (node (ref "U1") (pin "25") (pinfunction "VCC_25") (pintype "power_in"))
      (node (ref "U1") (pin "35") (pinfunction "VCC_35") (pintype "power_in"))
      (node (ref "U1") (pin "45") (pinfunction "VCC_45") (pintype "power_in"))
      (node (ref "U1") (pin "53") (pinfunction "VCC_53") (pintype "power_in"))
      (node (ref "U1") (pin "61") (pinfunction "AVCC_61") (pintype "power_in"))
    )
    (net (code "100") (name "/XTAL1") (class "Default")
      (node (ref "C1") (pin "2") (pinfunction "2_2") (pintype "passive"))
      (node (ref "Q1") (pin "1") (pinfunction "1_1") (pintype "passive"))
      (node (ref "U1") (pin "58") (pinfunction "PR0_58") (pintype "bidirectional"))
    )
    (net (code "101") (name "/XTAL2") (class "Default")
      (node (ref "C2") (pin "2") (pinfunction "2_2") (pintype "passive"))
      (node (ref "Q1") (pin "2") (pinfunction "2_2") (pintype "passive"))
      (node (ref "U1") (pin "59") (pinfunction "PR1_59") (pintype "bidirectional"))
    )
    (net (code "102") (name "Net-(IC1-R)") (class "Default")
      (node (ref "IC1") (pin "1") (pinfunction "R_1") (pintype "input"))
      (node (ref "OK1") (pin "3") (pinfunction "C_3") (pintype "passive"))
    )
    (net (code "103") (name "Net-(IC2-R)") (class "Default")
      (node (ref "IC2") (pin "1") (pinfunction "R_1") (pintype "input"))
      (node (ref "OK3") (pin "3") (pinfunction "C_3") (pintype "passive"))
    )
    (net (code "104") (name "Net-(IC3-R)") (class "Default")
      (node (ref "IC3") (pin "1") (pinfunction "R_1") (pintype "input"))
      (node (ref "OK5") (pin "3") (pinfunction "C_3") (pintype "passive"))
    )
    (net (code "105") (name "Net-(IC4-R)") (class "Default")
      (node (ref "IC4") (pin "1") (pinfunction "R_1") (pintype "input"))
      (node (ref "OK7") (pin "3") (pinfunction "C_3") (pintype "passive"))
    )
    (net (code "106") (name "Net-(OK1-A)") (class "Default")
      (node (ref "OK1") (pin "2") (pinfunction "A_2") (pintype "passive"))
      (node (ref "R49") (pin "2") (pinfunction "2_2") (pintype "passive"))
    )
    (net (code "107") (name "Net-(OK2A-A1)") (class "Default")
      (node (ref "OK2") (pin "1") (pinfunction "A1_1") (pintype "passive"))
      (node (ref "R35") (pin "1") (pinfunction "1_1") (pintype "passive"))
    )
    (net (code "108") (name "Net-(OK2B-A2)") (class "Default")
      (node (ref "OK2") (pin "4") (pinfunction "A2_4") (pintype "passive"))
      (node (ref "R36") (pin "1") (pinfunction "1_1") (pintype "passive"))
    )
    (net (code "109") (name "Net-(OK3-A)") (class "Default")
      (node (ref "OK3") (pin "2") (pinfunction "A_2") (pintype "passive"))
      (node (ref "R27") (pin "2") (pinfunction "2_2") (pintype "passive"))
    )
    (net (code "110") (name "Net-(OK4A-A1)") (class "Default")
      (node (ref "OK4") (pin "1") (pinfunction "A1_1") (pintype "passive"))
      (node (ref "R37") (pin "1") (pinfunction "1_1") (pintype "passive"))
    )
    (net (code "111") (name "Net-(OK4B-A2)") (class "Default")
      (node (ref "OK4") (pin "4") (pinfunction "A2_4") (pintype "passive"))
      (node (ref "R38") (pin "1") (pinfunction "1_1") (pintype "passive"))
    )
    (net (code "112") (name "Net-(OK5-A)") (class "Default")
      (node (ref "OK5") (pin "2") (pinfunction "A_2") (pintype "passive"))
      (node (ref "R30") (pin "2") (pinfunction "2_2") (pintype "passive"))
    )
    (net (code "113") (name "Net-(OK6A-A1)") (class "Default")
      (node (ref "OK6") (pin "1") (pinfunction "A1_1") (pintype "passive"))
      (node (ref "R39") (pin "1") (pinfunction "1_1") (pintype "passive"))
    )
    (net (code "114") (name "Net-(OK6B-A2)") (class "Default")
      (node (ref "OK6") (pin "4") (pinfunction "A2_4") (pintype "passive"))
      (node (ref "R40") (pin "1") (pinfunction "1_1") (pintype "passive"))
    )
    (net (code "115") (name "Net-(OK7-A)") (class "Default")
      (node (ref "OK7") (pin "2") (pinfunction "A_2") (pintype "passive"))
      (node (ref "R31") (pin "2") (pinfunction "2_2") (pintype "passive"))
    )
    (net (code "116") (name "Net-(OK9A-A1)") (class "Default")
      (node (ref "OK9") (pin "1") (pinfunction "A1_1") (pintype "passive"))
      (node (ref "R33") (pin "1") (pinfunction "1_1") (pintype "passive"))
    )
    (net (code "117") (name "Net-(OK9B-A2)") (class "Default")
      (node (ref "OK9") (pin "4") (pinfunction "A2_4") (pintype "passive"))
      (node (ref "R34") (pin "1") (pinfunction "1_1") (pintype "passive"))
    )
    (net (code "118") (name "Net-(PAD19-P)") (class "Default")
      (node (ref "PAD19") (pin "1") (pinfunction "P_1") (pintype "passive"))
      (node (ref "X3") (pin "1") (pinfunction "KL_1") (pintype "passive"))
    )
    (net (code "119") (name "Net-(PAD20-P)") (class "Default")
      (node (ref "PAD20") (pin "1") (pinfunction "P_1") (pintype "passive"))
      (node (ref "X3") (pin "2") (pinfunction "KL_2") (pintype "passive"))
    )
    (net (code "120") (name "Net-(PAD21-P)") (class "Default")
      (node (ref "PAD21") (pin "1") (pinfunction "P_1") (pintype "passive"))
      (node (ref "X3") (pin "3") (pinfunction "KL_3") (pintype "passive"))
    )
    (net (code "121") (name "Net-(PAD22-P)") (class "Default")
      (node (ref "PAD22") (pin "1") (pinfunction "P_1") (pintype "passive"))
      (node (ref "X3") (pin "4") (pinfunction "KL_4") (pintype "passive"))
    )
    (net (code "122") (name "Net-(PAD23-P)") (class "Default")
      (node (ref "PAD23") (pin "1") (pinfunction "P_1") (pintype "passive"))
      (node (ref "X3") (pin "5") (pinfunction "KL_5") (pintype "passive"))
    )
    (net (code "123") (name "Net-(PAD24-P)") (class "Default")
      (node (ref "PAD24") (pin "1") (pinfunction "P_1") (pintype "passive"))
      (node (ref "X3") (pin "6") (pinfunction "KL_6") (pintype "passive"))
    )
    (net (code "124") (name "Net-(PAD25-P)") (class "Default")
      (node (ref "PAD25") (pin "1") (pinfunction "P_1") (pintype "passive"))
      (node (ref "X3") (pin "7") (pinfunction "KL_7") (pintype "passive"))
    )
    (net (code "125") (name "Net-(PAD26-P)") (class "Default")
      (node (ref "PAD26") (pin "1") (pinfunction "P_1") (pintype "passive"))
      (node (ref "X4") (pin "1") (pinfunction "KL_1") (pintype "passive"))
    )
    (net (code "126") (name "Net-(PAD27-P)") (class "Default")
      (node (ref "PAD27") (pin "1") (pinfunction "P_1") (pintype "passive"))
      (node (ref "X4") (pin "2") (pinfunction "KL_2") (pintype "passive"))
    )
    (net (code "127") (name "Net-(PAD28-P)") (class "Default")
      (node (ref "PAD28") (pin "1") (pinfunction "P_1") (pintype "passive"))
      (node (ref "X4") (pin "3") (pinfunction "KL_3") (pintype "passive"))
    )
    (net (code "128") (name "Net-(PAD29-P)") (class "Default")
      (node (ref "PAD29") (pin "1") (pinfunction "P_1") (pintype "passive"))
      (node (ref "X4") (pin "4") (pinfunction "KL_4") (pintype "passive"))
    )
    (net (code "129") (name "Net-(PAD30-P)") (class "Default")
      (node (ref "PAD30") (pin "1") (pinfunction "P_1") (pintype "passive"))
      (node (ref "X4") (pin "5") (pinfunction "KL_5") (pintype "passive"))
    )
    (net (code "130") (name "Net-(PAD31-P)") (class "Default")
      (node (ref "PAD31") (pin "1") (pinfunction "P_1") (pintype "passive"))
      (node (ref "X4") (pin "6") (pinfunction "KL_6") (pintype "passive"))
    )
    (net (code "131") (name "Net-(PAD32-P)") (class "Default")
      (node (ref "PAD32") (pin "1") (pinfunction "P_1") (pintype "passive"))
      (node (ref "X4") (pin "7") (pinfunction "KL_7") (pintype "passive"))
    )
    (net (code "132") (name "unconnected-(IC1-~{RE}-Pad2)") (class "Default")
      (node (ref "IC1") (pin "2") (pinfunction "~{RE}_2") (pintype "input"))
    )
    (net (code "133") (name "unconnected-(IC2-~{RE}-Pad2)") (class "Default")
      (node (ref "IC2") (pin "2") (pinfunction "~{RE}_2") (pintype "input"))
    )
    (net (code "134") (name "unconnected-(IC3-~{RE}-Pad2)") (class "Default")
      (node (ref "IC3") (pin "2") (pinfunction "~{RE}_2") (pintype "input"))
    )
    (net (code "135") (name "unconnected-(IC4-~{RE}-Pad2)") (class "Default")
      (node (ref "IC4") (pin "2") (pinfunction "~{RE}_2") (pintype "input"))
    )
    (net (code "136") (name "unconnected-(OK1-VE-Pad7)") (class "Default")
      (node (ref "OK1") (pin "7") (pinfunction "VE_7") (pintype "passive"))
    )
    (net (code "137") (name "unconnected-(OK3-VE-Pad7)") (class "Default")
      (node (ref "OK3") (pin "7") (pinfunction "VE_7") (pintype "passive"))
    )
    (net (code "138") (name "unconnected-(OK5-VE-Pad7)") (class "Default")
      (node (ref "OK5") (pin "7") (pinfunction "VE_7") (pintype "passive"))
    )
    (net (code "139") (name "unconnected-(OK7-VE-Pad7)") (class "Default")
      (node (ref "OK7") (pin "7") (pinfunction "VE_7") (pintype "passive"))
    )
  )
)
